# prot-atmel-rev8_Display_PowerTip.net
KiCad netlist of a schematic drawn in EAGLE
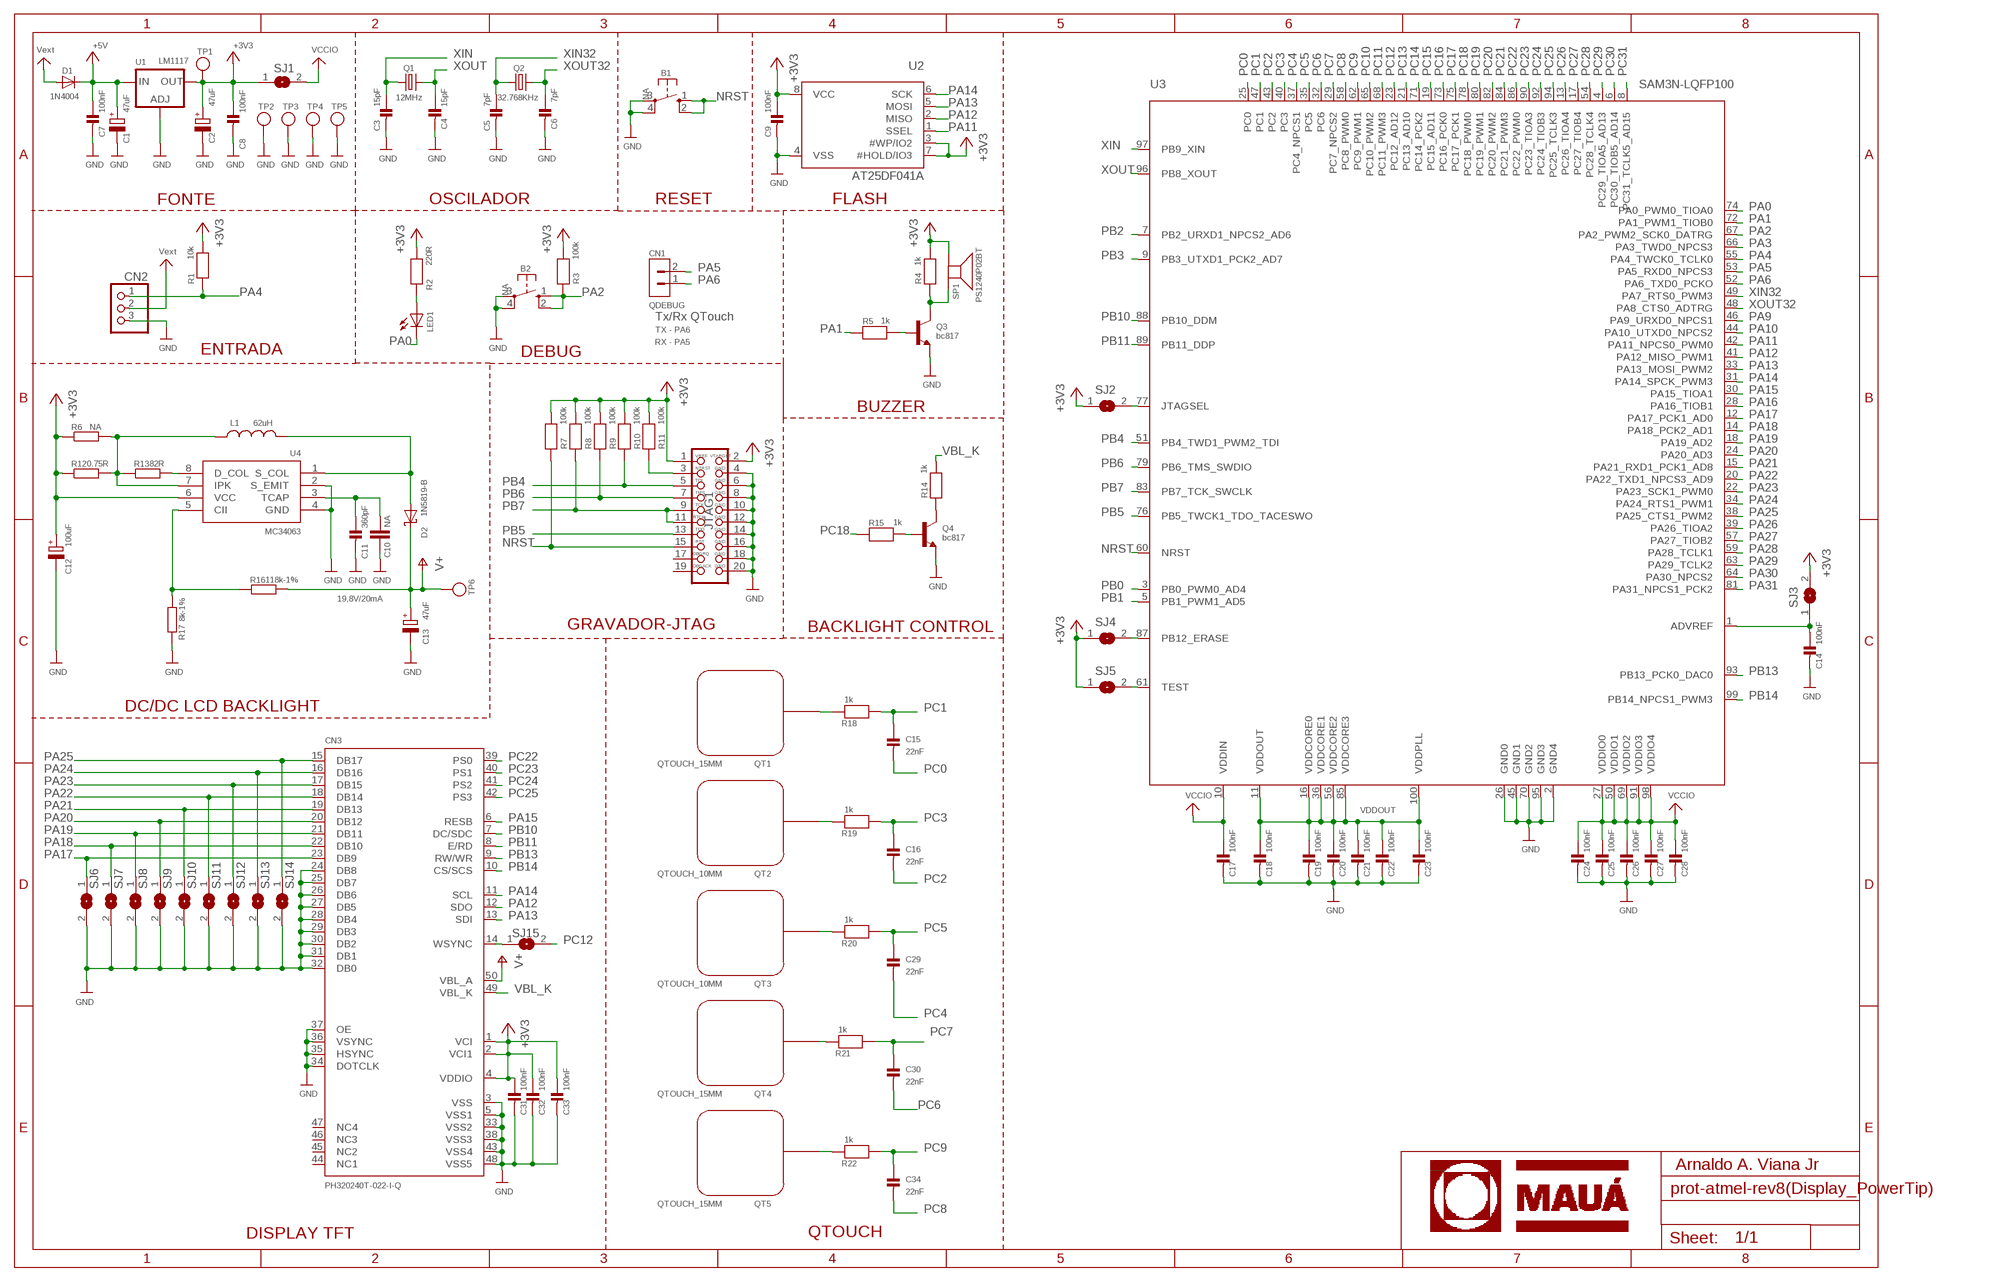
[diagram p0: schematic, sheet 1]

(export (version "E")
  (design (tool "Eeschema 10.0.6"))
  (components
    (comp (ref "B1")
      (value "NA")
      (footprint "eagle-import:B3F-10XX")
      (fields (field (name "MPN") "B3F-1000"))
      (libsource (lib "eagle-import") (part "10-XX"))
    )
    (comp (ref "B2")
      (value "NA")
      (footprint "eagle-import:B3F-10XX")
      (fields (field (name "MPN") "B3F-1000"))
      (libsource (lib "eagle-import") (part "10-XX"))
    )
    (comp (ref "C1")
      (value "47uF")
      (footprint "eagle-import:E2,5-6")
      (libsource (lib "eagle-import") (part "CPOL-EUE2.5-6"))
    )
    (comp (ref "C2")
      (value "47uF")
      (footprint "eagle-import:E2,5-6")
      (libsource (lib "eagle-import") (part "CPOL-EUE2.5-6"))
    )
    (comp (ref "C3")
      (value "15pF")
      (footprint "eagle-import:0805")
      (libsource (lib "eagle-import") (part "CAP_CERAMIC0805"))
    )
    (comp (ref "C4")
      (value "15pF")
      (footprint "eagle-import:0805")
      (libsource (lib "eagle-import") (part "CAP_CERAMIC0805"))
    )
    (comp (ref "C5")
      (value "7pF")
      (footprint "eagle-import:0805")
      (libsource (lib "eagle-import") (part "CAP_CERAMIC0805"))
    )
    (comp (ref "C6")
      (value "7pF")
      (footprint "eagle-import:0805")
      (libsource (lib "eagle-import") (part "CAP_CERAMIC0805"))
    )
    (comp (ref "C7")
      (value "100nF")
      (footprint "eagle-import:0805")
      (libsource (lib "eagle-import") (part "CAP_CERAMIC0805"))
    )
    (comp (ref "C8")
      (value "100nF")
      (footprint "eagle-import:0805")
      (libsource (lib "eagle-import") (part "CAP_CERAMIC0805"))
    )
    (comp (ref "C9")
      (value "100nF")
      (footprint "eagle-import:0805")
      (libsource (lib "eagle-import") (part "CAP_CERAMIC0805"))
    )
    (comp (ref "C10")
      (value "NA")
      (footprint "eagle-import:C025-025X050")
      (libsource (lib "eagle-import") (part "C-EU025-025X050"))
    )
    (comp (ref "C11")
      (value "360pF")
      (footprint "eagle-import:0805")
      (libsource (lib "eagle-import") (part "CAP_CERAMIC0805"))
    )
    (comp (ref "C12")
      (value "100uF")
      (footprint "eagle-import:E2,5-6")
      (libsource (lib "eagle-import") (part "CPOL-EUE2.5-6"))
    )
    (comp (ref "C13")
      (value "47uF")
      (footprint "eagle-import:E2,5-6")
      (libsource (lib "eagle-import") (part "CPOL-EUE2.5-6"))
    )
    (comp (ref "C14")
      (value "100nF")
      (footprint "eagle-import:0805")
      (libsource (lib "eagle-import") (part "CAP_CERAMIC0805"))
    )
    (comp (ref "C15")
      (value "22nF")
      (footprint "eagle-import:0805")
      (libsource (lib "eagle-import") (part "CAP_CERAMIC0805"))
    )
    (comp (ref "C16")
      (value "22nF")
      (footprint "eagle-import:0805")
      (libsource (lib "eagle-import") (part "CAP_CERAMIC0805"))
    )
    (comp (ref "C17")
      (value "100nF")
      (footprint "eagle-import:0805")
      (libsource (lib "eagle-import") (part "CAP_CERAMIC0805"))
    )
    (comp (ref "C18")
      (value "100nF")
      (footprint "eagle-import:0805")
      (libsource (lib "eagle-import") (part "CAP_CERAMIC0805"))
    )
    (comp (ref "C19")
      (value "100nF")
      (footprint "eagle-import:0805")
      (libsource (lib "eagle-import") (part "CAP_CERAMIC0805"))
    )
    (comp (ref "C20")
      (value "100nF")
      (footprint "eagle-import:0805")
      (libsource (lib "eagle-import") (part "CAP_CERAMIC0805"))
    )
    (comp (ref "C21")
      (value "100nF")
      (footprint "eagle-import:0805")
      (libsource (lib "eagle-import") (part "CAP_CERAMIC0805"))
    )
    (comp (ref "C22")
      (value "100nF")
      (footprint "eagle-import:0805")
      (libsource (lib "eagle-import") (part "CAP_CERAMIC0805"))
    )
    (comp (ref "C23")
      (value "100nF")
      (footprint "eagle-import:0805")
      (libsource (lib "eagle-import") (part "CAP_CERAMIC0805"))
    )
    (comp (ref "C24")
      (value "100nF")
      (footprint "eagle-import:0805")
      (libsource (lib "eagle-import") (part "CAP_CERAMIC0805"))
    )
    (comp (ref "C25")
      (value "100nF")
      (footprint "eagle-import:0805")
      (libsource (lib "eagle-import") (part "CAP_CERAMIC0805"))
    )
    (comp (ref "C26")
      (value "100nF")
      (footprint "eagle-import:0805")
      (libsource (lib "eagle-import") (part "CAP_CERAMIC0805"))
    )
    (comp (ref "C27")
      (value "100nF")
      (footprint "eagle-import:0805")
      (libsource (lib "eagle-import") (part "CAP_CERAMIC0805"))
    )
    (comp (ref "C28")
      (value "100nF")
      (footprint "eagle-import:0805")
      (libsource (lib "eagle-import") (part "CAP_CERAMIC0805"))
    )
    (comp (ref "C29")
      (value "22nF")
      (footprint "eagle-import:0805")
      (libsource (lib "eagle-import") (part "CAP_CERAMIC0805"))
    )
    (comp (ref "C30")
      (value "22nF")
      (footprint "eagle-import:0805")
      (libsource (lib "eagle-import") (part "CAP_CERAMIC0805"))
    )
    (comp (ref "C31")
      (value "100nF")
      (footprint "eagle-import:0805")
      (libsource (lib "eagle-import") (part "CAP_CERAMIC0805"))
    )
    (comp (ref "C32")
      (value "100nF")
      (footprint "eagle-import:0805")
      (libsource (lib "eagle-import") (part "CAP_CERAMIC0805"))
    )
    (comp (ref "C33")
      (value "100nF")
      (footprint "eagle-import:0805")
      (libsource (lib "eagle-import") (part "CAP_CERAMIC0805"))
    )
    (comp (ref "C34")
      (value "22nF")
      (footprint "eagle-import:0805")
      (libsource (lib "eagle-import") (part "CAP_CERAMIC0805"))
    )
    (comp (ref "CN1")
      (value "QDEBUG")
      (footprint "eagle-import:HEADER_1X02")
      (libsource (lib "eagle-import") (part "HEADER_1X02"))
    )
    (comp (ref "CN2")
      (value "HEADER-1X3")
      (footprint "eagle-import:1X03_OVAL")
      (libsource (lib "eagle-import") (part "HEADER-1X3"))
    )
    (comp (ref "CN3")
      (value "PH320240T-022-I-Q")
      (footprint "eagle-import:FPC50PIN_TFT-PH320240T")
      (libsource (lib "eagle-import") (part "DISP_TFT_PH320240T-022-I-QTOP"))
    )
    (comp (ref "D1")
      (value "1N4004")
      (footprint "eagle-import:D-5")
      (libsource (lib "eagle-import") (part "DIODE-D-5"))
    )
    (comp (ref "D2")
      (value "1N5819-B")
      (footprint "eagle-import:DO41-7.6")
      (libsource (lib "eagle-import") (part "1N5819-B"))
    )
    (comp (ref "JTAG1")
      (value "JTAG-ARM")
      (footprint "eagle-import:JTAG-ARM")
      (libsource (lib "eagle-import") (part "JTAG-ARM"))
    )
    (comp (ref "L1")
      (value "62uH")
      (footprint "eagle-import:0204_5")
      (libsource (lib "eagle-import") (part "L-US0204/5"))
    )
    (comp (ref "LED1")
      (value "LEDSML0805")
      (footprint "eagle-import:SML0805")
      (libsource (lib "eagle-import") (part "LEDSML0805"))
    )
    (comp (ref "Q1")
      (value "12MHz")
      (footprint "eagle-import:HC49_S")
      (libsource (lib "eagle-import") (part "CRYSTALHC49S"))
    )
    (comp (ref "Q2")
      (value "32.768KHz")
      (footprint "eagle-import:TC26V")
      (libsource (lib "eagle-import") (part "CRYSTALTC26V"))
    )
    (comp (ref "Q3")
      (value "bc817")
      (footprint "eagle-import:SOT23-W")
      (libsource (lib "eagle-import") (part "TRANSISTOR_NPNWAVE"))
    )
    (comp (ref "Q4")
      (value "bc817")
      (footprint "eagle-import:SOT23-W")
      (libsource (lib "eagle-import") (part "TRANSISTOR_NPNWAVE"))
    )
    (comp (ref "QT1")
      (value "QTOUCH_15MM")
      (footprint "eagle-import:BUTTON_15MM")
      (libsource (lib "eagle-import") (part "QTOUCH_15MM"))
    )
    (comp (ref "QT2")
      (value "QTOUCH_10MM")
      (footprint "eagle-import:BUTTON_10MM")
      (libsource (lib "eagle-import") (part "QTOUCH_10MM"))
    )
    (comp (ref "QT3")
      (value "QTOUCH_10MM")
      (footprint "eagle-import:BUTTON_10MM")
      (libsource (lib "eagle-import") (part "QTOUCH_10MM"))
    )
    (comp (ref "QT4")
      (value "QTOUCH_15MM")
      (footprint "eagle-import:BUTTON_15MM")
      (libsource (lib "eagle-import") (part "QTOUCH_15MM"))
    )
    (comp (ref "QT5")
      (value "QTOUCH_15MM")
      (footprint "eagle-import:BUTTON_15MM")
      (libsource (lib "eagle-import") (part "QTOUCH_15MM"))
    )
    (comp (ref "R1")
      (value "10k")
      (footprint "eagle-import:_0805")
      (libsource (lib "eagle-import") (part "RESISTOR_0805"))
    )
    (comp (ref "R2")
      (value "220R")
      (footprint "eagle-import:_0805")
      (libsource (lib "eagle-import") (part "RESISTOR_0805"))
    )
    (comp (ref "R3")
      (value "100k")
      (footprint "eagle-import:_0805")
      (libsource (lib "eagle-import") (part "RESISTOR_0805"))
    )
    (comp (ref "R4")
      (value "1k")
      (footprint "eagle-import:_0805")
      (libsource (lib "eagle-import") (part "RESISTOR_0805"))
    )
    (comp (ref "R5")
      (value "1k")
      (footprint "eagle-import:_0805")
      (libsource (lib "eagle-import") (part "RESISTOR_0805"))
    )
    (comp (ref "R6")
      (value "NA")
      (footprint "eagle-import:0204_5")
      (libsource (lib "eagle-import") (part "R-EU_0204/5"))
    )
    (comp (ref "R7")
      (value "100k")
      (footprint "eagle-import:_0805")
      (libsource (lib "eagle-import") (part "RESISTOR_0805"))
    )
    (comp (ref "R8")
      (value "100k")
      (footprint "eagle-import:_0805")
      (libsource (lib "eagle-import") (part "RESISTOR_0805"))
    )
    (comp (ref "R9")
      (value "100k")
      (footprint "eagle-import:_0805")
      (libsource (lib "eagle-import") (part "RESISTOR_0805"))
    )
    (comp (ref "R10")
      (value "100k")
      (footprint "eagle-import:_0805")
      (libsource (lib "eagle-import") (part "RESISTOR_0805"))
    )
    (comp (ref "R11")
      (value "100k")
      (footprint "eagle-import:_0805")
      (libsource (lib "eagle-import") (part "RESISTOR_0805"))
    )
    (comp (ref "R12")
      (value "0.75R")
      (footprint "eagle-import:R1218")
      (libsource (lib "eagle-import") (part "R-EU_R1218"))
    )
    (comp (ref "R13")
      (value "82R")
      (footprint "eagle-import:M0805")
      (libsource (lib "eagle-import") (part "R-EU_M0805"))
    )
    (comp (ref "R14")
      (value "1k")
      (footprint "eagle-import:_0805")
      (libsource (lib "eagle-import") (part "RESISTOR_0805"))
    )
    (comp (ref "R15")
      (value "1k")
      (footprint "eagle-import:_0805")
      (libsource (lib "eagle-import") (part "RESISTOR_0805"))
    )
    (comp (ref "R16")
      (value "118k-1%")
      (footprint "eagle-import:M0805")
      (libsource (lib "eagle-import") (part "R-EU_M0805"))
    )
    (comp (ref "R17")
      (value "8k-1%")
      (footprint "eagle-import:M0805")
      (libsource (lib "eagle-import") (part "R-EU_M0805"))
    )
    (comp (ref "R18")
      (value "1k")
      (footprint "eagle-import:_0805")
      (libsource (lib "eagle-import") (part "RESISTOR_0805"))
    )
    (comp (ref "R19")
      (value "1k")
      (footprint "eagle-import:_0805")
      (libsource (lib "eagle-import") (part "RESISTOR_0805"))
    )
    (comp (ref "R20")
      (value "1k")
      (footprint "eagle-import:_0805")
      (libsource (lib "eagle-import") (part "RESISTOR_0805"))
    )
    (comp (ref "R21")
      (value "1k")
      (footprint "eagle-import:_0805")
      (libsource (lib "eagle-import") (part "RESISTOR_0805"))
    )
    (comp (ref "R22")
      (value "1k")
      (footprint "eagle-import:_0805")
      (libsource (lib "eagle-import") (part "RESISTOR_0805"))
    )
    (comp (ref "SJ1")
      (value "SOLDERJUMPER")
      (footprint "eagle-import:SOLDERJUMPER_ARROW_NOPASTE")
      (libsource (lib "eagle-import") (part "SOLDERJUMPER"))
    )
    (comp (ref "SJ2")
      (value "SOLDERJUMPER")
      (footprint "eagle-import:SOLDERJUMPER_ARROW_NOPASTE")
      (libsource (lib "eagle-import") (part "SOLDERJUMPER"))
    )
    (comp (ref "SJ3")
      (value "SOLDERJUMPER")
      (footprint "eagle-import:SOLDERJUMPER_ARROW_NOPASTE")
      (libsource (lib "eagle-import") (part "SOLDERJUMPER"))
    )
    (comp (ref "SJ4")
      (value "SOLDERJUMPER")
      (footprint "eagle-import:SOLDERJUMPER_ARROW_NOPASTE")
      (libsource (lib "eagle-import") (part "SOLDERJUMPER"))
    )
    (comp (ref "SJ5")
      (value "SOLDERJUMPER")
      (footprint "eagle-import:SOLDERJUMPER_ARROW_NOPASTE")
      (libsource (lib "eagle-import") (part "SOLDERJUMPER"))
    )
    (comp (ref "SJ6")
      (value "SOLDERJUMPER")
      (footprint "eagle-import:SOLDERJUMPER_ARROW_NOPASTE")
      (fields (field (name "BOM") "EXCLUDE"))
      (libsource (lib "eagle-import") (part "SOLDERJUMPER"))
    )
    (comp (ref "SJ7")
      (value "SOLDERJUMPER")
      (footprint "eagle-import:SOLDERJUMPER_ARROW_NOPASTE")
      (fields (field (name "BOM") "EXCLUDE"))
      (libsource (lib "eagle-import") (part "SOLDERJUMPER"))
    )
    (comp (ref "SJ8")
      (value "SOLDERJUMPER")
      (footprint "eagle-import:SOLDERJUMPER_ARROW_NOPASTE")
      (fields (field (name "BOM") "EXCLUDE"))
      (libsource (lib "eagle-import") (part "SOLDERJUMPER"))
    )
    (comp (ref "SJ9")
      (value "SOLDERJUMPER")
      (footprint "eagle-import:SOLDERJUMPER_ARROW_NOPASTE")
      (fields (field (name "BOM") "EXCLUDE"))
      (libsource (lib "eagle-import") (part "SOLDERJUMPER"))
    )
    (comp (ref "SJ10")
      (value "SOLDERJUMPER")
      (footprint "eagle-import:SOLDERJUMPER_ARROW_NOPASTE")
      (fields (field (name "BOM") "EXCLUDE"))
      (libsource (lib "eagle-import") (part "SOLDERJUMPER"))
    )
    (comp (ref "SJ11")
      (value "SOLDERJUMPER")
      (footprint "eagle-import:SOLDERJUMPER_ARROW_NOPASTE")
      (fields (field (name "BOM") "EXCLUDE"))
      (libsource (lib "eagle-import") (part "SOLDERJUMPER"))
    )
    (comp (ref "SJ12")
      (value "SOLDERJUMPER")
      (footprint "eagle-import:SOLDERJUMPER_ARROW_NOPASTE")
      (fields (field (name "BOM") "EXCLUDE"))
      (libsource (lib "eagle-import") (part "SOLDERJUMPER"))
    )
    (comp (ref "SJ13")
      (value "SOLDERJUMPER")
      (footprint "eagle-import:SOLDERJUMPER_ARROW_NOPASTE")
      (fields (field (name "BOM") "EXCLUDE"))
      (libsource (lib "eagle-import") (part "SOLDERJUMPER"))
    )
    (comp (ref "SJ14")
      (value "SOLDERJUMPER")
      (footprint "eagle-import:SOLDERJUMPER_ARROW_NOPASTE")
      (fields (field (name "BOM") "EXCLUDE"))
      (libsource (lib "eagle-import") (part "SOLDERJUMPER"))
    )
    (comp (ref "SJ15")
      (value "SOLDERJUMPER")
      (footprint "eagle-import:SOLDERJUMPER_ARROW_NOPASTE")
      (fields (field (name "BOM") "EXCLUDE"))
      (libsource (lib "eagle-import") (part "SOLDERJUMPER"))
    )
    (comp (ref "SP1")
      (value "PS1240P02BT")
      (footprint "eagle-import:PS1240P02BT")
      (libsource (lib "eagle-import") (part "PS1240P02BT"))
    )
    (comp (ref "TP1")
      (value "+3V3")
      (footprint "eagle-import:1X01_ROUND")
      (libsource (lib "eagle-import") (part "TESTPOINT0.1{dblquote}"))
    )
    (comp (ref "TP2")
      (value "GND")
      (footprint "eagle-import:1X01_ROUND")
      (fields (field (name "BOM") "EXCLUDE"))
      (libsource (lib "eagle-import") (part "TESTPOINT0.1{dblquote}"))
    )
    (comp (ref "TP3")
      (value "GND")
      (footprint "eagle-import:1X01_ROUND")
      (fields (field (name "BOM") "EXCLUDE"))
      (libsource (lib "eagle-import") (part "TESTPOINT0.1{dblquote}"))
    )
    (comp (ref "TP4")
      (value "GND")
      (footprint "eagle-import:1X01_ROUND")
      (fields (field (name "BOM") "EXCLUDE"))
      (libsource (lib "eagle-import") (part "TESTPOINT0.1{dblquote}"))
    )
    (comp (ref "TP5")
      (value "GND")
      (footprint "eagle-import:1X01_ROUND")
      (fields (field (name "BOM") "EXCLUDE"))
      (libsource (lib "eagle-import") (part "TESTPOINT0.1{dblquote}"))
    )
    (comp (ref "TP6")
      (value "+V")
      (footprint "eagle-import:1X01_ROUND")
      (libsource (lib "eagle-import") (part "TESTPOINT0.1{dblquote}"))
    )
    (comp (ref "U1")
      (value "LM1117")
      (footprint "eagle-import:TO252")
      (libsource (lib "eagle-import") (part "LM1117TO252"))
    )
    (comp (ref "U2")
      (value "AT25DF041A")
      (footprint "eagle-import:SOIC8_208MIL")
      (libsource (lib "eagle-import") (part "SPIFLASH_SOIC8208MIL"))
    )
    (comp (ref "U3")
      (value "SAM3N-LQFP100")
      (footprint "eagle-import:LQFP100")
      (libsource (lib "eagle-import") (part "SAM3N-LQFP100"))
    )
    (comp (ref "U4")
      (value "MC34063")
      (footprint "eagle-import:SOIC8_150MIL")
      (libsource (lib "eagle-import") (part "MC34063A"))
    )
  )
  (nets
    (net (code "1") (name "+3V3") (class "Default")
      (node (ref "C12") (pin "+") (pinfunction "+_+") (pintype "passive"))
      (node (ref "C2") (pin "+") (pinfunction "+_+") (pintype "passive"))
      (node (ref "C31") (pin "1") (pinfunction "P$1_1") (pintype "passive"))
      (node (ref "C32") (pin "1") (pinfunction "P$1_1") (pintype "passive"))
      (node (ref "C33") (pin "1") (pinfunction "P$1_1") (pintype "passive"))
      (node (ref "C8") (pin "1") (pinfunction "P$1_1") (pintype "passive"))
      (node (ref "C9") (pin "1") (pinfunction "P$1_1") (pintype "passive"))
      (node (ref "CN3") (pin "1") (pinfunction "VCI_1") (pintype "power_in"))
      (node (ref "CN3") (pin "2") (pinfunction "VCI1_2") (pintype "power_in"))
      (node (ref "CN3") (pin "4") (pinfunction "VDDIO_4") (pintype "power_in"))
      (node (ref "JTAG1") (pin "1") (pinfunction "1_1") (pintype "passive"))
      (node (ref "JTAG1") (pin "2") (pinfunction "2_2") (pintype "passive"))
      (node (ref "R1") (pin "2") (pinfunction "2_2") (pintype "passive"))
      (node (ref "R10") (pin "2") (pinfunction "2_2") (pintype "passive"))
      (node (ref "R11") (pin "2") (pinfunction "2_2") (pintype "passive"))
      (node (ref "R12") (pin "1") (pinfunction "1_1") (pintype "passive"))
      (node (ref "R2") (pin "2") (pinfunction "2_2") (pintype "passive"))
      (node (ref "R3") (pin "2") (pinfunction "2_2") (pintype "passive"))
      (node (ref "R4") (pin "2") (pinfunction "2_2") (pintype "passive"))
      (node (ref "R6") (pin "1") (pinfunction "1_1") (pintype "passive"))
      (node (ref "R7") (pin "2") (pinfunction "2_2") (pintype "passive"))
      (node (ref "R8") (pin "2") (pinfunction "2_2") (pintype "passive"))
      (node (ref "R9") (pin "2") (pinfunction "2_2") (pintype "passive"))
      (node (ref "SJ1") (pin "1") (pinfunction "1_1") (pintype "passive"))
      (node (ref "SJ2") (pin "1") (pinfunction "1_1") (pintype "passive"))
      (node (ref "SJ3") (pin "2") (pinfunction "2_2") (pintype "passive"))
      (node (ref "SJ4") (pin "1") (pinfunction "1_1") (pintype "passive"))
      (node (ref "SJ5") (pin "1") (pinfunction "1_1") (pintype "passive"))
      (node (ref "SP1") (pin "P$2") (pinfunction "P$2_P$2") (pintype "bidirectional"))
      (node (ref "TP1") (pin "1") (pinfunction "P$1_1") (pintype "bidirectional"))
      (node (ref "U1") (pin "3") (pinfunction "OUT_3") (pintype "passive"))
      (node (ref "U2") (pin "3") (pinfunction "#WP/IO2_3") (pintype "bidirectional"))
      (node (ref "U2") (pin "7") (pinfunction "#HOLD/IO3_7") (pintype "bidirectional"))
      (node (ref "U2") (pin "8") (pinfunction "VCC_8") (pintype "bidirectional"))
      (node (ref "U4") (pin "6") (pinfunction "VCC_6") (pintype "bidirectional"))
    )
    (net (code "2") (name "+5V") (class "Default")
      (node (ref "C1") (pin "+") (pinfunction "+_+") (pintype "passive"))
      (node (ref "C7") (pin "1") (pinfunction "P$1_1") (pintype "passive"))
      (node (ref "D1") (pin "C") (pinfunction "C_C") (pintype "passive"))
      (node (ref "U1") (pin "2") (pinfunction "IN_2") (pintype "input"))
    )
    (net (code "3") (name "/NRST") (class "Default")
      (node (ref "B1") (pin "1") (pinfunction "S_1") (pintype "passive"))
      (node (ref "B1") (pin "2") (pinfunction "S1_2") (pintype "passive"))
      (node (ref "JTAG1") (pin "15") (pinfunction "15_15") (pintype "passive"))
      (node (ref "R7") (pin "1") (pinfunction "1_1") (pintype "passive"))
      (node (ref "U3") (pin "60") (pinfunction "NRST_60") (pintype "bidirectional"))
    )
    (net (code "4") (name "/PA0") (class "Default")
      (node (ref "LED1") (pin "C") (pinfunction "C_C") (pintype "passive"))
      (node (ref "U3") (pin "74") (pinfunction "PA0_PWM0_TIOA0_74") (pintype "bidirectional"))
    )
    (net (code "5") (name "/PA1") (class "Default")
      (node (ref "R5") (pin "2") (pinfunction "2_2") (pintype "passive"))
      (node (ref "U3") (pin "72") (pinfunction "PA1_PWM1_TIOB0_72") (pintype "bidirectional"))
    )
    (net (code "6") (name "/PA2") (class "Default")
      (node (ref "B2") (pin "1") (pinfunction "S_1") (pintype "passive"))
      (node (ref "B2") (pin "2") (pinfunction "S1_2") (pintype "passive"))
      (node (ref "R3") (pin "1") (pinfunction "1_1") (pintype "passive"))
      (node (ref "U3") (pin "67") (pinfunction "PA2_PWM2_SCK0_DATRG_67") (pintype "bidirectional"))
    )
    (net (code "7") (name "/PA3") (class "Default")
      (node (ref "U3") (pin "66") (pinfunction "PA3_TWD0_NPCS3_66") (pintype "bidirectional"))
    )
    (net (code "8") (name "/PA4") (class "Default")
      (node (ref "CN2") (pin "1") (pinfunction "1_1") (pintype "passive"))
      (node (ref "R1") (pin "1") (pinfunction "1_1") (pintype "passive"))
      (node (ref "U3") (pin "55") (pinfunction "PA4_TWCK0_TCLK0_55") (pintype "bidirectional"))
    )
    (net (code "9") (name "/PA5") (class "Default")
      (node (ref "CN1") (pin "2") (pinfunction "2_2") (pintype "passive"))
      (node (ref "U3") (pin "53") (pinfunction "PA5_RXD0_NPCS3_53") (pintype "bidirectional"))
    )
    (net (code "10") (name "/PA6") (class "Default")
      (node (ref "CN1") (pin "1") (pinfunction "1_1") (pintype "passive"))
      (node (ref "U3") (pin "52") (pinfunction "PA6_TXD0_PCKO_52") (pintype "bidirectional"))
    )
    (net (code "11") (name "/PA9") (class "Default")
      (node (ref "U3") (pin "46") (pinfunction "PA9_URXD0_NPCS1_46") (pintype "bidirectional"))
    )
    (net (code "12") (name "/PA10") (class "Default")
      (node (ref "U3") (pin "44") (pinfunction "PA10_UTXD0_NPCS2_44") (pintype "bidirectional"))
    )
    (net (code "13") (name "/PA11") (class "Default")
      (node (ref "U2") (pin "1") (pinfunction "SSEL_1") (pintype "bidirectional"))
      (node (ref "U3") (pin "42") (pinfunction "PA11_NPCS0_PWM0_42") (pintype "bidirectional"))
    )
    (net (code "14") (name "/PA12") (class "Default")
      (node (ref "CN3") (pin "12") (pinfunction "SDO_12") (pintype "bidirectional"))
      (node (ref "U2") (pin "2") (pinfunction "MISO_2") (pintype "bidirectional"))
      (node (ref "U3") (pin "41") (pinfunction "PA12_MISO_PWM1_41") (pintype "bidirectional"))
    )
    (net (code "15") (name "/PA13") (class "Default")
      (node (ref "CN3") (pin "13") (pinfunction "SDI_13") (pintype "bidirectional"))
      (node (ref "U2") (pin "5") (pinfunction "MOSI_5") (pintype "bidirectional"))
      (node (ref "U3") (pin "33") (pinfunction "PA13_MOSI_PWM2_33") (pintype "bidirectional"))
    )
    (net (code "16") (name "/PA14") (class "Default")
      (node (ref "CN3") (pin "11") (pinfunction "SCL_11") (pintype "bidirectional"))
      (node (ref "U2") (pin "6") (pinfunction "SCK_6") (pintype "bidirectional"))
      (node (ref "U3") (pin "31") (pinfunction "PA14_SPCK_PWM3_31") (pintype "bidirectional"))
    )
    (net (code "17") (name "/PA15") (class "Default")
      (node (ref "CN3") (pin "6") (pinfunction "RESB_6") (pintype "bidirectional"))
      (node (ref "U3") (pin "30") (pinfunction "PA15_TIOA1_30") (pintype "bidirectional"))
    )
    (net (code "18") (name "/PA16") (class "Default")
      (node (ref "U3") (pin "28") (pinfunction "PA16_TIOB1_28") (pintype "bidirectional"))
    )
    (net (code "19") (name "/PA17") (class "Default")
      (node (ref "CN3") (pin "23") (pinfunction "DB9_23") (pintype "bidirectional"))
      (node (ref "SJ6") (pin "1") (pinfunction "1_1") (pintype "passive"))
      (node (ref "U3") (pin "12") (pinfunction "PA17_PCK1_AD0_12") (pintype "bidirectional"))
    )
    (net (code "20") (name "/PA18") (class "Default")
      (node (ref "CN3") (pin "22") (pinfunction "DB10_22") (pintype "bidirectional"))
      (node (ref "SJ7") (pin "1") (pinfunction "1_1") (pintype "passive"))
      (node (ref "U3") (pin "14") (pinfunction "PA18_PCK2_AD1_14") (pintype "bidirectional"))
    )
    (net (code "21") (name "/PA19") (class "Default")
      (node (ref "CN3") (pin "21") (pinfunction "DB11_21") (pintype "bidirectional"))
      (node (ref "SJ8") (pin "1") (pinfunction "1_1") (pintype "passive"))
      (node (ref "U3") (pin "18") (pinfunction "PA19_AD2_18") (pintype "bidirectional"))
    )
    (net (code "22") (name "/PA20") (class "Default")
      (node (ref "CN3") (pin "20") (pinfunction "DB12_20") (pintype "bidirectional"))
      (node (ref "SJ9") (pin "1") (pinfunction "1_1") (pintype "passive"))
      (node (ref "U3") (pin "24") (pinfunction "PA20_AD3_24") (pintype "bidirectional"))
    )
    (net (code "23") (name "/PA21") (class "Default")
      (node (ref "CN3") (pin "19") (pinfunction "DB13_19") (pintype "bidirectional"))
      (node (ref "SJ10") (pin "1") (pinfunction "1_1") (pintype "passive"))
      (node (ref "U3") (pin "15") (pinfunction "PA21_RXD1_PCK1_AD8_15") (pintype "bidirectional"))
    )
    (net (code "24") (name "/PA22") (class "Default")
      (node (ref "CN3") (pin "18") (pinfunction "DB14_18") (pintype "bidirectional"))
      (node (ref "SJ11") (pin "1") (pinfunction "1_1") (pintype "passive"))
      (node (ref "U3") (pin "20") (pinfunction "PA22_TXD1_NPCS3_AD9_20") (pintype "bidirectional"))
    )
    (net (code "25") (name "/PA23") (class "Default")
      (node (ref "CN3") (pin "17") (pinfunction "DB15_17") (pintype "bidirectional"))
      (node (ref "SJ12") (pin "1") (pinfunction "1_1") (pintype "passive"))
      (node (ref "U3") (pin "22") (pinfunction "PA23_SCK1_PWM0_22") (pintype "bidirectional"))
    )
    (net (code "26") (name "/PA24") (class "Default")
      (node (ref "CN3") (pin "16") (pinfunction "DB16_16") (pintype "bidirectional"))
      (node (ref "SJ13") (pin "1") (pinfunction "1_1") (pintype "passive"))
      (node (ref "U3") (pin "34") (pinfunction "PA24_RTS1_PWM1_34") (pintype "bidirectional"))
    )
    (net (code "27") (name "/PA25") (class "Default")
      (node (ref "CN3") (pin "15") (pinfunction "DB17_15") (pintype "bidirectional"))
      (node (ref "SJ14") (pin "1") (pinfunction "1_1") (pintype "passive"))
      (node (ref "U3") (pin "38") (pinfunction "PA25_CTS1_PWM2_38") (pintype "bidirectional"))
    )
    (net (code "28") (name "/PA26") (class "Default")
      (node (ref "U3") (pin "39") (pinfunction "PA26_TIOA2_39") (pintype "bidirectional"))
    )
    (net (code "29") (name "/PA27") (class "Default")
      (node (ref "U3") (pin "57") (pinfunction "PA27_TIOB2_57") (pintype "bidirectional"))
    )
    (net (code "30") (name "/PA28") (class "Default")
      (node (ref "U3") (pin "59") (pinfunction "PA28_TCLK1_59") (pintype "bidirectional"))
    )
    (net (code "31") (name "/PA29") (class "Default")
      (node (ref "U3") (pin "63") (pinfunction "PA29_TCLK2_63") (pintype "bidirectional"))
    )
    (net (code "32") (name "/PA30") (class "Default")
      (node (ref "U3") (pin "64") (pinfunction "PA30_NPCS2_64") (pintype "bidirectional"))
    )
    (net (code "33") (name "/PA31") (class "Default")
      (node (ref "U3") (pin "81") (pinfunction "PA31_NPCS1_PCK2_81") (pintype "bidirectional"))
    )
    (net (code "34") (name "/PB0") (class "Default")
      (node (ref "U3") (pin "3") (pinfunction "PB0_PWM0_AD4_3") (pintype "bidirectional"))
    )
    (net (code "35") (name "/PB1") (class "Default")
      (node (ref "U3") (pin "5") (pinfunction "PB1_PWM1_AD5_5") (pintype "bidirectional"))
    )
    (net (code "36") (name "/PB2") (class "Default")
      (node (ref "U3") (pin "7") (pinfunction "PB2_URXD1_NPCS2_AD6_7") (pintype "bidirectional"))
    )
    (net (code "37") (name "/PB3") (class "Default")
      (node (ref "U3") (pin "9") (pinfunction "PB3_UTXD1_PCK2_AD7_9") (pintype "bidirectional"))
    )
    (net (code "38") (name "/PB4") (class "Default")
      (node (ref "JTAG1") (pin "5") (pinfunction "5_5") (pintype "passive"))
      (node (ref "R10") (pin "1") (pinfunction "1_1") (pintype "passive"))
      (node (ref "U3") (pin "51") (pinfunction "PB4_TWD1_PWM2_TDI_51") (pintype "bidirectional"))
    )
    (net (code "39") (name "/PB5") (class "Default")
      (node (ref "JTAG1") (pin "13") (pinfunction "13_13") (pintype "passive"))
      (node (ref "U3") (pin "76") (pinfunction "PB5_TWCK1_TDO_TACESWO_76") (pintype "bidirectional"))
    )
    (net (code "40") (name "/PB6") (class "Default")
      (node (ref "JTAG1") (pin "7") (pinfunction "7_7") (pintype "passive"))
      (node (ref "R9") (pin "1") (pinfunction "1_1") (pintype "passive"))
      (node (ref "U3") (pin "79") (pinfunction "PB6_TMS_SWDIO_79") (pintype "bidirectional"))
    )
    (net (code "41") (name "/PB7") (class "Default")
      (node (ref "JTAG1") (pin "11") (pinfunction "11_11") (pintype "passive"))
      (node (ref "JTAG1") (pin "9") (pinfunction "9_9") (pintype "passive"))
      (node (ref "R8") (pin "1") (pinfunction "1_1") (pintype "passive"))
      (node (ref "U3") (pin "83") (pinfunction "PB7_TCK_SWCLK_83") (pintype "bidirectional"))
    )
    (net (code "42") (name "/PB10") (class "Default")
      (node (ref "CN3") (pin "7") (pinfunction "DC/SDC_7") (pintype "bidirectional"))
      (node (ref "U3") (pin "88") (pinfunction "PB10_DDM_88") (pintype "bidirectional"))
    )
    (net (code "43") (name "/PB11") (class "Default")
      (node (ref "CN3") (pin "8") (pinfunction "E/RD_8") (pintype "bidirectional"))
      (node (ref "U3") (pin "89") (pinfunction "PB11_DDP_89") (pintype "bidirectional"))
    )
    (net (code "44") (name "/PB13") (class "Default")
      (node (ref "CN3") (pin "9") (pinfunction "RW/WR_9") (pintype "bidirectional"))
      (node (ref "U3") (pin "93") (pinfunction "PB13_PCK0_DAC0_93") (pintype "bidirectional"))
    )
    (net (code "45") (name "/PB14") (class "Default")
      (node (ref "CN3") (pin "10") (pinfunction "CS/SCS_10") (pintype "bidirectional"))
      (node (ref "U3") (pin "99") (pinfunction "PB14_NPCS1_PWM3_99") (pintype "bidirectional"))
    )
    (net (code "46") (name "/PC0") (class "Default")
      (node (ref "C15") (pin "2") (pinfunction "P$2_2") (pintype "passive"))
      (node (ref "U3") (pin "25") (pinfunction "PC0_25") (pintype "bidirectional"))
    )
    (net (code "47") (name "/PC1") (class "Default")
      (node (ref "C15") (pin "1") (pinfunction "P$1_1") (pintype "passive"))
      (node (ref "R18") (pin "1") (pinfunction "1_1") (pintype "passive"))
      (node (ref "U3") (pin "47") (pinfunction "PC1_47") (pintype "bidirectional"))
    )
    (net (code "48") (name "/PC2") (class "Default")
      (node (ref "C16") (pin "2") (pinfunction "P$2_2") (pintype "passive"))
      (node (ref "U3") (pin "43") (pinfunction "PC2_43") (pintype "bidirectional"))
    )
    (net (code "49") (name "/PC3") (class "Default")
      (node (ref "C16") (pin "1") (pinfunction "P$1_1") (pintype "passive"))
      (node (ref "R19") (pin "1") (pinfunction "1_1") (pintype "passive"))
      (node (ref "U3") (pin "40") (pinfunction "PC3_40") (pintype "bidirectional"))
    )
    (net (code "50") (name "/PC4") (class "Default")
      (node (ref "C29") (pin "2") (pinfunction "P$2_2") (pintype "passive"))
      (node (ref "U3") (pin "37") (pinfunction "PC4_NPCS1_37") (pintype "bidirectional"))
    )
    (net (code "51") (name "/PC5") (class "Default")
      (node (ref "C29") (pin "1") (pinfunction "P$1_1") (pintype "passive"))
      (node (ref "R20") (pin "1") (pinfunction "1_1") (pintype "passive"))
      (node (ref "U3") (pin "35") (pinfunction "PC5_35") (pintype "bidirectional"))
    )
    (net (code "52") (name "/PC6") (class "Default")
      (node (ref "C30") (pin "2") (pinfunction "P$2_2") (pintype "passive"))
      (node (ref "U3") (pin "32") (pinfunction "PC6_32") (pintype "bidirectional"))
    )
    (net (code "53") (name "/PC7") (class "Default")
      (node (ref "C30") (pin "1") (pinfunction "P$1_1") (pintype "passive"))
      (node (ref "R21") (pin "1") (pinfunction "1_1") (pintype "passive"))
      (node (ref "U3") (pin "29") (pinfunction "PC7_NPCS2_29") (pintype "bidirectional"))
    )
    (net (code "54") (name "/PC8") (class "Default")
      (node (ref "C34") (pin "2") (pinfunction "P$2_2") (pintype "passive"))
      (node (ref "U3") (pin "58") (pinfunction "PC8_PWM0_58") (pintype "bidirectional"))
    )
    (net (code "55") (name "/PC9") (class "Default")
      (node (ref "C34") (pin "1") (pinfunction "P$1_1") (pintype "passive"))
      (node (ref "R22") (pin "1") (pinfunction "1_1") (pintype "passive"))
      (node (ref "U3") (pin "62") (pinfunction "PC9_PWM1_62") (pintype "bidirectional"))
    )
    (net (code "56") (name "/PC10") (class "Default")
      (node (ref "U3") (pin "65") (pinfunction "PC10_PWM2_65") (pintype "bidirectional"))
    )
    (net (code "57") (name "/PC11") (class "Default")
      (node (ref "U3") (pin "68") (pinfunction "PC11_PWM3_68") (pintype "bidirectional"))
    )
    (net (code "58") (name "/PC12") (class "Default")
      (node (ref "SJ15") (pin "2") (pinfunction "2_2") (pintype "passive"))
      (node (ref "U3") (pin "23") (pinfunction "PC12_AD12_23") (pintype "bidirectional"))
    )
    (net (code "59") (name "/PC13") (class "Default")
      (node (ref "U3") (pin "21") (pinfunction "PC13_AD10_21") (pintype "bidirectional"))
    )
    (net (code "60") (name "/PC14") (class "Default")
      (node (ref "U3") (pin "71") (pinfunction "PC14_PCK2_71") (pintype "bidirectional"))
    )
    (net (code "61") (name "/PC15") (class "Default")
      (node (ref "U3") (pin "19") (pinfunction "PC15_AD11_19") (pintype "bidirectional"))
    )
    (net (code "62") (name "/PC16") (class "Default")
      (node (ref "U3") (pin "73") (pinfunction "PC16_PCK0_73") (pintype "bidirectional"))
    )
    (net (code "63") (name "/PC17") (class "Default")
      (node (ref "U3") (pin "75") (pinfunction "PC17_PCK1_75") (pintype "bidirectional"))
    )
    (net (code "64") (name "/PC18") (class "Default")
      (node (ref "R15") (pin "1") (pinfunction "1_1") (pintype "passive"))
      (node (ref "U3") (pin "78") (pinfunction "PC18_PWM0_78") (pintype "bidirectional"))
    )
    (net (code "65") (name "/PC19") (class "Default")
      (node (ref "U3") (pin "80") (pinfunction "PC19_PWM1_80") (pintype "bidirectional"))
    )
    (net (code "66") (name "/PC20") (class "Default")
      (node (ref "U3") (pin "82") (pinfunction "PC20_PWM2_82") (pintype "bidirectional"))
    )
    (net (code "67") (name "/PC21") (class "Default")
      (node (ref "U3") (pin "84") (pinfunction "PC21_PWM3_84") (pintype "bidirectional"))
    )
    (net (code "68") (name "/PC22") (class "Default")
      (node (ref "CN3") (pin "39") (pinfunction "PS0_39") (pintype "bidirectional"))
      (node (ref "U3") (pin "86") (pinfunction "PC22_PWM0_86") (pintype "bidirectional"))
    )
    (net (code "69") (name "/PC23") (class "Default")
      (node (ref "CN3") (pin "40") (pinfunction "PS1_40") (pintype "bidirectional"))
      (node (ref "U3") (pin "90") (pinfunction "PC23_TIOA3_90") (pintype "bidirectional"))
    )
    (net (code "70") (name "/PC24") (class "Default")
      (node (ref "CN3") (pin "41") (pinfunction "PS2_41") (pintype "bidirectional"))
      (node (ref "U3") (pin "92") (pinfunction "PC24_TIOB3_92") (pintype "bidirectional"))
    )
    (net (code "71") (name "/PC25") (class "Default")
      (node (ref "CN3") (pin "42") (pinfunction "PS3_42") (pintype "bidirectional"))
      (node (ref "U3") (pin "94") (pinfunction "PC25_TCLK3_94") (pintype "bidirectional"))
    )
    (net (code "72") (name "/PC26") (class "Default")
      (node (ref "U3") (pin "13") (pinfunction "PC26_TIOA4_13") (pintype "bidirectional"))
    )
    (net (code "73") (name "/PC27") (class "Default")
      (node (ref "U3") (pin "17") (pinfunction "PC27_TIOB4_17") (pintype "bidirectional"))
    )
    (net (code "74") (name "/PC28") (class "Default")
      (node (ref "U3") (pin "54") (pinfunction "PC28_TCLK4_54") (pintype "bidirectional"))
    )
    (net (code "75") (name "/PC29") (class "Default")
      (node (ref "U3") (pin "4") (pinfunction "PC29_TIOA5_AD13_4") (pintype "bidirectional"))
    )
    (net (code "76") (name "/PC30") (class "Default")
      (node (ref "U3") (pin "6") (pinfunction "PC30_TIOB5_AD14_6") (pintype "bidirectional"))
    )
    (net (code "77") (name "/PC31") (class "Default")
      (node (ref "U3") (pin "8") (pinfunction "PC31_TCLK5_AD15_8") (pintype "bidirectional"))
    )
    (net (code "78") (name "/VBL_K") (class "Default")
      (node (ref "CN3") (pin "49") (pinfunction "VBL_K_49") (pintype "bidirectional"))
      (node (ref "R14") (pin "2") (pinfunction "2_2") (pintype "passive"))
    )
    (net (code "79") (name "/VDDOUT") (class "Default")
      (node (ref "C18") (pin "1") (pinfunction "P$1_1") (pintype "passive"))
      (node (ref "C19") (pin "1") (pinfunction "P$1_1") (pintype "passive"))
      (node (ref "C20") (pin "1") (pinfunction "P$1_1") (pintype "passive"))
      (node (ref "C21") (pin "1") (pinfunction "P$1_1") (pintype "passive"))
      (node (ref "C22") (pin "1") (pinfunction "P$1_1") (pintype "passive"))
      (node (ref "C23") (pin "1") (pinfunction "P$1_1") (pintype "passive"))
      (node (ref "U3") (pin "100") (pinfunction "VDDPLL_100") (pintype "bidirectional"))
      (node (ref "U3") (pin "11") (pinfunction "VDDOUT_11") (pintype "bidirectional"))
      (node (ref "U3") (pin "16") (pinfunction "VDDCORE0_16") (pintype "bidirectional"))
      (node (ref "U3") (pin "36") (pinfunction "VDDCORE1_36") (pintype "bidirectional"))
      (node (ref "U3") (pin "56") (pinfunction "VDDCORE2_56") (pintype "bidirectional"))
      (node (ref "U3") (pin "85") (pinfunction "VDDCORE3_85") (pintype "bidirectional"))
    )
    (net (code "80") (name "/XIN") (class "Default")
      (node (ref "C3") (pin "1") (pinfunction "P$1_1") (pintype "passive"))
      (node (ref "Q1") (pin "1") (pinfunction "1_1") (pintype "passive"))
      (node (ref "U3") (pin "97") (pinfunction "PB9_XIN_97") (pintype "bidirectional"))
    )
    (net (code "81") (name "/XIN32") (class "Default")
      (node (ref "C5") (pin "1") (pinfunction "P$1_1") (pintype "passive"))
      (node (ref "Q2") (pin "1") (pinfunction "1_1") (pintype "passive"))
      (node (ref "U3") (pin "49") (pinfunction "PA7_RTS0_PWM3_49") (pintype "bidirectional"))
    )
    (net (code "82") (name "/XOUT") (class "Default")
      (node (ref "C4") (pin "1") (pinfunction "P$1_1") (pintype "passive"))
      (node (ref "Q1") (pin "2") (pinfunction "2_2") (pintype "passive"))
      (node (ref "U3") (pin "96") (pinfunction "PB8_XOUT_96") (pintype "bidirectional"))
    )
    (net (code "83") (name "/XOUT32") (class "Default")
      (node (ref "C6") (pin "1") (pinfunction "P$1_1") (pintype "passive"))
      (node (ref "Q2") (pin "2") (pinfunction "2_2") (pintype "passive"))
      (node (ref "U3") (pin "48") (pinfunction "PA8_CTS0_ADTRG_48") (pintype "bidirectional"))
    )
    (net (code "84") (name "GND") (class "Default")
      (node (ref "B1") (pin "3") (pinfunction "P_3") (pintype "passive"))
      (node (ref "B1") (pin "4") (pinfunction "P1_4") (pintype "passive"))
      (node (ref "B2") (pin "3") (pinfunction "P_3") (pintype "passive"))
      (node (ref "B2") (pin "4") (pinfunction "P1_4") (pintype "passive"))
      (node (ref "C1") (pin "-") (pinfunction "-_-") (pintype "passive"))
      (node (ref "C10") (pin "2") (pinfunction "2_2") (pintype "passive"))
      (node (ref "C11") (pin "2") (pinfunction "P$2_2") (pintype "passive"))
      (node (ref "C12") (pin "-") (pinfunction "-_-") (pintype "passive"))
      (node (ref "C13") (pin "-") (pinfunction "-_-") (pintype "passive"))
      (node (ref "C14") (pin "2") (pinfunction "P$2_2") (pintype "passive"))
      (node (ref "C17") (pin "2") (pinfunction "P$2_2") (pintype "passive"))
      (node (ref "C18") (pin "2") (pinfunction "P$2_2") (pintype "passive"))
      (node (ref "C19") (pin "2") (pinfunction "P$2_2") (pintype "passive"))
      (node (ref "C2") (pin "-") (pinfunction "-_-") (pintype "passive"))
      (node (ref "C20") (pin "2") (pinfunction "P$2_2") (pintype "passive"))
      (node (ref "C21") (pin "2") (pinfunction "P$2_2") (pintype "passive"))
      (node (ref "C22") (pin "2") (pinfunction "P$2_2") (pintype "passive"))
      (node (ref "C23") (pin "2") (pinfunction "P$2_2") (pintype "passive"))
      (node (ref "C24") (pin "2") (pinfunction "P$2_2") (pintype "passive"))
      (node (ref "C25") (pin "2") (pinfunction "P$2_2") (pintype "passive"))
      (node (ref "C26") (pin "2") (pinfunction "P$2_2") (pintype "passive"))
      (node (ref "C27") (pin "2") (pinfunction "P$2_2") (pintype "passive"))
      (node (ref "C28") (pin "2") (pinfunction "P$2_2") (pintype "passive"))
      (node (ref "C3") (pin "2") (pinfunction "P$2_2") (pintype "passive"))
      (node (ref "C31") (pin "2") (pinfunction "P$2_2") (pintype "passive"))
      (node (ref "C32") (pin "2") (pinfunction "P$2_2") (pintype "passive"))
      (node (ref "C33") (pin "2") (pinfunction "P$2_2") (pintype "passive"))
      (node (ref "C4") (pin "2") (pinfunction "P$2_2") (pintype "passive"))
      (node (ref "C5") (pin "2") (pinfunction "P$2_2") (pintype "passive"))
      (node (ref "C6") (pin "2") (pinfunction "P$2_2") (pintype "passive"))
      (node (ref "C7") (pin "2") (pinfunction "P$2_2") (pintype "passive"))
      (node (ref "C8") (pin "2") (pinfunction "P$2_2") (pintype "passive"))
      (node (ref "C9") (pin "2") (pinfunction "P$2_2") (pintype "passive"))
      (node (ref "CN2") (pin "3") (pinfunction "3_3") (pintype "passive"))
      (node (ref "CN3") (pin "24") (pinfunction "DB8_24") (pintype "bidirectional"))
      (node (ref "CN3") (pin "25") (pinfunction "DB7_25") (pintype "bidirectional"))
      (node (ref "CN3") (pin "26") (pinfunction "DB6_26") (pintype "bidirectional"))
      (node (ref "CN3") (pin "27") (pinfunction "DB5_27") (pintype "bidirectional"))
      (node (ref "CN3") (pin "28") (pinfunction "DB4_28") (pintype "bidirectional"))
      (node (ref "CN3") (pin "29") (pinfunction "DB3_29") (pintype "bidirectional"))
      (node (ref "CN3") (pin "3") (pinfunction "VSS_3") (pintype "power_in"))
      (node (ref "CN3") (pin "30") (pinfunction "DB2_30") (pintype "bidirectional"))
      (node (ref "CN3") (pin "31") (pinfunction "DB1_31") (pintype "bidirectional"))
      (node (ref "CN3") (pin "32") (pinfunction "DB0_32") (pintype "bidirectional"))
      (node (ref "CN3") (pin "33") (pinfunction "VSS2_33") (pintype "power_in"))
      (node (ref "CN3") (pin "34") (pinfunction "DOTCLK_34") (pintype "bidirectional"))
      (node (ref "CN3") (pin "35") (pinfunction "HSYNC_35") (pintype "bidirectional"))
      (node (ref "CN3") (pin "36") (pinfunction "VSYNC_36") (pintype "bidirectional"))
      (node (ref "CN3") (pin "37") (pinfunction "OE_37") (pintype "bidirectional"))
      (node (ref "CN3") (pin "38") (pinfunction "VSS3_38") (pintype "power_in"))
      (node (ref "CN3") (pin "43") (pinfunction "VSS4_43") (pintype "power_in"))
      (node (ref "CN3") (pin "48") (pinfunction "VSS5_48") (pintype "power_in"))
      (node (ref "CN3") (pin "5") (pinfunction "VSS1_5") (pintype "power_in"))
      (node (ref "JTAG1") (pin "10") (pinfunction "10_10") (pintype "passive"))
      (node (ref "JTAG1") (pin "12") (pinfunction "12_12") (pintype "passive"))
      (node (ref "JTAG1") (pin "14") (pinfunction "14_14") (pintype "passive"))
      (node (ref "JTAG1") (pin "16") (pinfunction "16_16") (pintype "passive"))
      (node (ref "JTAG1") (pin "18") (pinfunction "18_18") (pintype "passive"))
      (node (ref "JTAG1") (pin "20") (pinfunction "20_20") (pintype "passive"))
      (node (ref "JTAG1") (pin "4") (pinfunction "4_4") (pintype "passive"))
      (node (ref "JTAG1") (pin "6") (pinfunction "6_6") (pintype "passive"))
      (node (ref "JTAG1") (pin "8") (pinfunction "8_8") (pintype "passive"))
      (node (ref "Q3") (pin "2") (pinfunction "E_2") (pintype "passive"))
      (node (ref "Q4") (pin "2") (pinfunction "E_2") (pintype "passive"))
      (node (ref "R17") (pin "1") (pinfunction "1_1") (pintype "passive"))
      (node (ref "SJ10") (pin "2") (pinfunction "2_2") (pintype "passive"))
      (node (ref "SJ11") (pin "2") (pinfunction "2_2") (pintype "passive"))
      (node (ref "SJ12") (pin "2") (pinfunction "2_2") (pintype "passive"))
      (node (ref "SJ13") (pin "2") (pinfunction "2_2") (pintype "passive"))
      (node (ref "SJ14") (pin "2") (pinfunction "2_2") (pintype "passive"))
      (node (ref "SJ6") (pin "2") (pinfunction "2_2") (pintype "passive"))
      (node (ref "SJ7") (pin "2") (pinfunction "2_2") (pintype "passive"))
      (node (ref "SJ8") (pin "2") (pinfunction "2_2") (pintype "passive"))
      (node (ref "SJ9") (pin "2") (pinfunction "2_2") (pintype "passive"))
      (node (ref "TP2") (pin "1") (pinfunction "P$1_1") (pintype "bidirectional"))
      (node (ref "TP3") (pin "1") (pinfunction "P$1_1") (pintype "bidirectional"))
      (node (ref "TP4") (pin "1") (pinfunction "P$1_1") (pintype "bidirectional"))
      (node (ref "TP5") (pin "1") (pinfunction "P$1_1") (pintype "bidirectional"))
      (node (ref "U1") (pin "1") (pinfunction "ADJ_1") (pintype "input"))
      (node (ref "U2") (pin "4") (pinfunction "VSS_4") (pintype "bidirectional"))
      (node (ref "U3") (pin "2") (pinfunction "GND4_2") (pintype "bidirectional"))
      (node (ref "U3") (pin "26") (pinfunction "GND0_26") (pintype "bidirectional"))
      (node (ref "U3") (pin "45") (pinfunction "GND1_45") (pintype "bidirectional"))
      (node (ref "U3") (pin "70") (pinfunction "GND2_70") (pintype "bidirectional"))
      (node (ref "U3") (pin "95") (pinfunction "GND3_95") (pintype "bidirectional"))
      (node (ref "U4") (pin "2") (pinfunction "S_EMIT_2") (pintype "bidirectional"))
      (node (ref "U4") (pin "4") (pinfunction "GND_4") (pintype "bidirectional"))
    )
    (net (code "85") (name "Net-(C11-P$1)") (class "Default")
      (node (ref "C10") (pin "1") (pinfunction "1_1") (pintype "passive"))
      (node (ref "C11") (pin "1") (pinfunction "P$1_1") (pintype "passive"))
      (node (ref "U4") (pin "3") (pinfunction "TCAP_3") (pintype "bidirectional"))
    )
    (net (code "86") (name "Net-(C14-P$1)") (class "Default")
      (node (ref "C14") (pin "1") (pinfunction "P$1_1") (pintype "passive"))
      (node (ref "SJ3") (pin "1") (pinfunction "1_1") (pintype "passive"))
      (node (ref "U3") (pin "1") (pinfunction "ADVREF_1") (pintype "bidirectional"))
    )
    (net (code "87") (name "Net-(CN3-WSYNC)") (class "Default")
      (node (ref "CN3") (pin "14") (pinfunction "WSYNC_14") (pintype "bidirectional"))
      (node (ref "SJ15") (pin "1") (pinfunction "1_1") (pintype "passive"))
    )
    (net (code "88") (name "Net-(JTAG1-Pad3)") (class "Default")
      (node (ref "JTAG1") (pin "3") (pinfunction "3_3") (pintype "passive"))
      (node (ref "R11") (pin "1") (pinfunction "1_1") (pintype "passive"))
    )
    (net (code "89") (name "Net-(LED1-PadA)") (class "Default")
      (node (ref "LED1") (pin "A") (pinfunction "A_A") (pintype "passive"))
      (node (ref "R2") (pin "1") (pinfunction "1_1") (pintype "passive"))
    )
    (net (code "90") (name "Net-(Q3-B)") (class "Default")
      (node (ref "Q3") (pin "1") (pinfunction "B_1") (pintype "passive"))
      (node (ref "R5") (pin "1") (pinfunction "1_1") (pintype "passive"))
    )
    (net (code "91") (name "Net-(Q3-C)") (class "Default")
      (node (ref "Q3") (pin "3") (pinfunction "C_3") (pintype "passive"))
      (node (ref "R4") (pin "1") (pinfunction "1_1") (pintype "passive"))
      (node (ref "SP1") (pin "P$1") (pinfunction "P$1_P$1") (pintype "bidirectional"))
    )
    (net (code "92") (name "Net-(Q4-B)") (class "Default")
      (node (ref "Q4") (pin "1") (pinfunction "B_1") (pintype "passive"))
      (node (ref "R15") (pin "2") (pinfunction "2_2") (pintype "passive"))
    )
    (net (code "93") (name "Net-(Q4-C)") (class "Default")
      (node (ref "Q4") (pin "3") (pinfunction "C_3") (pintype "passive"))
      (node (ref "R14") (pin "1") (pinfunction "1_1") (pintype "passive"))
    )
    (net (code "94") (name "Net-(QT1-P$3)") (class "Default")
      (node (ref "QT1") (pin "P$1") (pinfunction "P$3_P$1") (pintype "bidirectional"))
      (node (ref "R18") (pin "2") (pinfunction "2_2") (pintype "passive"))
    )
    (net (code "95") (name "Net-(QT2-P$3)") (class "Default")
      (node (ref "QT2") (pin "P$1") (pinfunction "P$3_P$1") (pintype "bidirectional"))
      (node (ref "R19") (pin "2") (pinfunction "2_2") (pintype "passive"))
    )
    (net (code "96") (name "Net-(QT3-P$3)") (class "Default")
      (node (ref "QT3") (pin "P$1") (pinfunction "P$3_P$1") (pintype "bidirectional"))
      (node (ref "R20") (pin "2") (pinfunction "2_2") (pintype "passive"))
    )
    (net (code "97") (name "Net-(QT4-P$3)") (class "Default")
      (node (ref "QT4") (pin "P$1") (pinfunction "P$3_P$1") (pintype "bidirectional"))
      (node (ref "R21") (pin "2") (pinfunction "2_2") (pintype "passive"))
    )
    (net (code "98") (name "Net-(QT5-P$3)") (class "Default")
      (node (ref "QT5") (pin "P$1") (pinfunction "P$3_P$1") (pintype "bidirectional"))
      (node (ref "R22") (pin "2") (pinfunction "2_2") (pintype "passive"))
    )
    (net (code "99") (name "Net-(U3-JTAGSEL)") (class "Default")
      (node (ref "SJ2") (pin "2") (pinfunction "2_2") (pintype "passive"))
      (node (ref "U3") (pin "77") (pinfunction "JTAGSEL_77") (pintype "bidirectional"))
    )
    (net (code "100") (name "Net-(U3-PB12_ERASE)") (class "Default")
      (node (ref "SJ4") (pin "2") (pinfunction "2_2") (pintype "passive"))
      (node (ref "U3") (pin "87") (pinfunction "PB12_ERASE_87") (pintype "bidirectional"))
    )
    (net (code "101") (name "Net-(U3-TEST)") (class "Default")
      (node (ref "SJ5") (pin "2") (pinfunction "2_2") (pintype "passive"))
      (node (ref "U3") (pin "61") (pinfunction "TEST_61") (pintype "bidirectional"))
    )
    (net (code "102") (name "Net-(U4-CII)") (class "Default")
      (node (ref "R16") (pin "1") (pinfunction "1_1") (pintype "passive"))
      (node (ref "R17") (pin "2") (pinfunction "2_2") (pintype "passive"))
      (node (ref "U4") (pin "5") (pinfunction "CII_5") (pintype "bidirectional"))
    )
    (net (code "103") (name "Net-(U4-D_COL)") (class "Default")
      (node (ref "R13") (pin "2") (pinfunction "2_2") (pintype "passive"))
      (node (ref "U4") (pin "8") (pinfunction "D_COL_8") (pintype "bidirectional"))
    )
    (net (code "104") (name "Net-(U4-IPK)") (class "Default")
      (node (ref "L1") (pin "1") (pinfunction "1_1") (pintype "passive"))
      (node (ref "R12") (pin "2") (pinfunction "2_2") (pintype "passive"))
      (node (ref "R13") (pin "1") (pinfunction "1_1") (pintype "passive"))
      (node (ref "R6") (pin "2") (pinfunction "2_2") (pintype "passive"))
      (node (ref "U4") (pin "7") (pinfunction "IPK_7") (pintype "bidirectional"))
    )
    (net (code "105") (name "Net-(U4-S_COL)") (class "Default")
      (node (ref "D2") (pin "A") (pinfunction "A_A") (pintype "passive"))
      (node (ref "L1") (pin "2") (pinfunction "2_2") (pintype "passive"))
      (node (ref "U4") (pin "1") (pinfunction "S_COL_1") (pintype "bidirectional"))
    )
    (net (code "106") (name "V+") (class "Default")
      (node (ref "C13") (pin "+") (pinfunction "+_+") (pintype "passive"))
      (node (ref "CN3") (pin "50") (pinfunction "VBL_A_50") (pintype "bidirectional"))
      (node (ref "D2") (pin "C") (pinfunction "C_C") (pintype "passive"))
      (node (ref "R16") (pin "2") (pinfunction "2_2") (pintype "passive"))
      (node (ref "TP6") (pin "1") (pinfunction "P$1_1") (pintype "bidirectional"))
    )
    (net (code "107") (name "VCCIO") (class "Default")
      (node (ref "C17") (pin "1") (pinfunction "P$1_1") (pintype "passive"))
      (node (ref "C24") (pin "1") (pinfunction "P$1_1") (pintype "passive"))
      (node (ref "C25") (pin "1") (pinfunction "P$1_1") (pintype "passive"))
      (node (ref "C26") (pin "1") (pinfunction "P$1_1") (pintype "passive"))
      (node (ref "C27") (pin "1") (pinfunction "P$1_1") (pintype "passive"))
      (node (ref "C28") (pin "1") (pinfunction "P$1_1") (pintype "passive"))
      (node (ref "SJ1") (pin "2") (pinfunction "2_2") (pintype "passive"))
      (node (ref "U3") (pin "10") (pinfunction "VDDIN_10") (pintype "bidirectional"))
      (node (ref "U3") (pin "27") (pinfunction "VDDIO0_27") (pintype "bidirectional"))
      (node (ref "U3") (pin "50") (pinfunction "VDDIO1_50") (pintype "bidirectional"))
      (node (ref "U3") (pin "69") (pinfunction "VDDIO2_69") (pintype "bidirectional"))
      (node (ref "U3") (pin "91") (pinfunction "VDDIO3_91") (pintype "bidirectional"))
      (node (ref "U3") (pin "98") (pinfunction "VDDIO4_98") (pintype "bidirectional"))
    )
    (net (code "108") (name "Vext") (class "Default")
      (node (ref "CN2") (pin "2") (pinfunction "2_2") (pintype "passive"))
      (node (ref "D1") (pin "A") (pinfunction "A_A") (pintype "passive"))
    )
    (net (code "109") (name "unconnected-(CN3-NC1-Pad44)") (class "Default")
      (node (ref "CN3") (pin "44") (pinfunction "NC1_44") (pintype "no_connect"))
    )
    (net (code "110") (name "unconnected-(CN3-NC2-Pad45)") (class "Default")
      (node (ref "CN3") (pin "45") (pinfunction "NC2_45") (pintype "no_connect"))
    )
    (net (code "111") (name "unconnected-(CN3-NC3-Pad46)") (class "Default")
      (node (ref "CN3") (pin "46") (pinfunction "NC3_46") (pintype "no_connect"))
    )
    (net (code "112") (name "unconnected-(CN3-NC4-Pad47)") (class "Default")
      (node (ref "CN3") (pin "47") (pinfunction "NC4_47") (pintype "no_connect"))
    )
    (net (code "113") (name "unconnected-(JTAG1-Pad17)") (class "Default")
      (node (ref "JTAG1") (pin "17") (pinfunction "17_17") (pintype "passive"))
    )
    (net (code "114") (name "unconnected-(JTAG1-Pad19)") (class "Default")
      (node (ref "JTAG1") (pin "19") (pinfunction "19_19") (pintype "passive"))
    )
  )
)
